# CCP_IO.net
KiCad netlist of a schematic drawn in Altium Designer
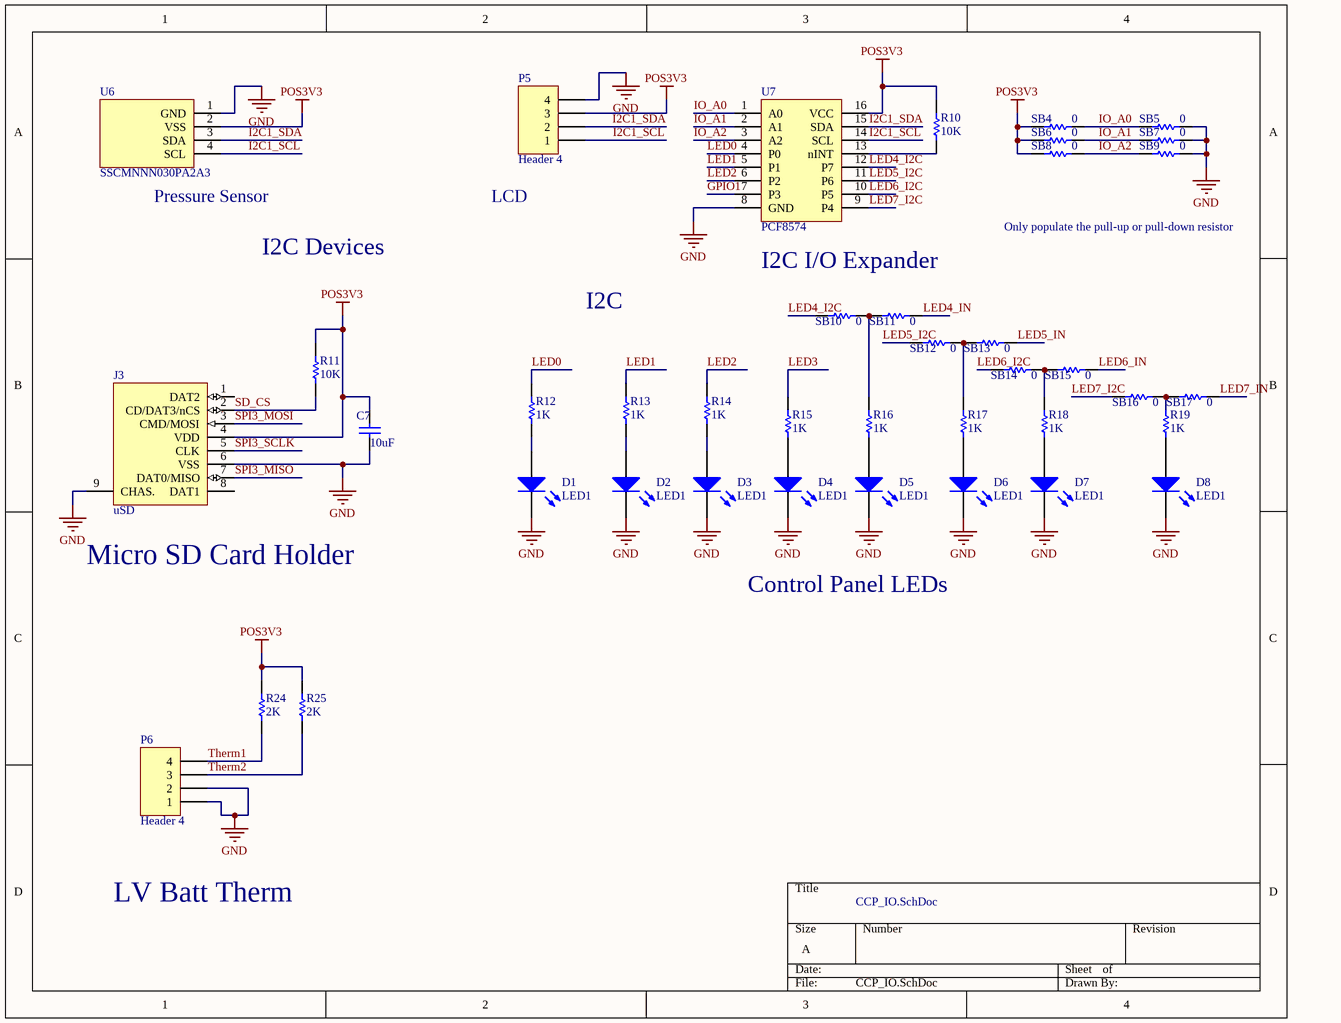
[diagram p0: CCP_IO.SchDoc]

(export (version "E")
  (design (tool "Eeschema 10.0.6"))
  (components
    (comp (ref "C7")
      (value "10uF")
      (footprint "C1206")
      (description "Capacitor")
      (fields (field (name "Comment") "Cap") (field (name "PUBLISHER") "Altium Limited"))
      (libsource (lib "Miscellaneous Devices") (part "Cap"))
    )
    (comp (ref "D1")
      (value "LED1")
      (footprint "2 Pin Jumper")
      (description "Typical RED GaAs LED")
      (fields (field (name "PUBLISHER") "Altium Limited"))
      (libsource (lib "Miscellaneous Devices") (part "LED1"))
    )
    (comp (ref "D2")
      (value "LED1")
      (footprint "2 Pin Jumper")
      (description "Typical RED GaAs LED")
      (fields (field (name "PUBLISHER") "Altium Limited"))
      (libsource (lib "Miscellaneous Devices") (part "LED1"))
    )
    (comp (ref "D3")
      (value "LED1")
      (footprint "2 Pin Jumper")
      (description "Typical RED GaAs LED")
      (fields (field (name "PUBLISHER") "Altium Limited"))
      (libsource (lib "Miscellaneous Devices") (part "LED1"))
    )
    (comp (ref "D4")
      (value "LED1")
      (footprint "2 Pin Jumper")
      (description "Typical RED GaAs LED")
      (fields (field (name "PUBLISHER") "Altium Limited"))
      (libsource (lib "Miscellaneous Devices") (part "LED1"))
    )
    (comp (ref "D5")
      (value "LED1")
      (footprint "2 Pin Jumper")
      (description "Typical RED GaAs LED")
      (fields (field (name "PUBLISHER") "Altium Limited"))
      (libsource (lib "Miscellaneous Devices") (part "LED1"))
    )
    (comp (ref "D6")
      (value "LED1")
      (footprint "2 Pin Jumper")
      (description "Typical RED GaAs LED")
      (fields (field (name "PUBLISHER") "Altium Limited"))
      (libsource (lib "Miscellaneous Devices") (part "LED1"))
    )
    (comp (ref "D7")
      (value "LED1")
      (footprint "2 Pin Jumper")
      (description "Typical RED GaAs LED")
      (fields (field (name "PUBLISHER") "Altium Limited"))
      (libsource (lib "Miscellaneous Devices") (part "LED1"))
    )
    (comp (ref "D8")
      (value "LED1")
      (footprint "2 Pin Jumper")
      (description "Typical RED GaAs LED")
      (fields (field (name "PUBLISHER") "Altium Limited"))
      (libsource (lib "Miscellaneous Devices") (part "LED1"))
    )
    (comp (ref "J3")
      (value "uSD")
      (footprint "MICRO_SD_HOLDER")
      (libsource (lib "connector") (part "SD Card"))
    )
    (comp (ref "P5")
      (value "Header 4")
      (footprint "4POS TERM BLOCK")
      (description "Header, 4-Pin")
      (fields (field (name "PUBLISHER") "Altium Limited"))
      (libsource (lib "Miscellaneous Connectors") (part "Header 4"))
    )
    (comp (ref "P6")
      (value "Header 4")
      (footprint "HDR1X4")
      (description "Header, 4-Pin")
      (fields (field (name "PUBLISHER") "Altium Limited"))
      (libsource (lib "Miscellaneous Connectors") (part "Header 4"))
    )
    (comp (ref "R10")
      (value "10K")
      (footprint "6-0805_M")
      (description "Resistor")
      (fields (field (name "Comment") "Res1") (field (name "PUBLISHER") "Altium Limited"))
      (libsource (lib "Miscellaneous Devices") (part "Res1"))
    )
    (comp (ref "R11")
      (value "10K")
      (footprint "6-0805_M")
      (description "Resistor")
      (fields (field (name "Comment") "Res1") (field (name "PUBLISHER") "Altium Limited"))
      (libsource (lib "Miscellaneous Devices") (part "Res1"))
    )
    (comp (ref "R12")
      (value "1K")
      (footprint "1206")
      (description "Resistor")
      (fields (field (name "Comment") "Res1") (field (name "PUBLISHER") "Altium Limited"))
      (libsource (lib "Miscellaneous Devices") (part "Res1"))
    )
    (comp (ref "R13")
      (value "1K")
      (footprint "1206")
      (description "Resistor")
      (fields (field (name "Comment") "Res1") (field (name "PUBLISHER") "Altium Limited"))
      (libsource (lib "Miscellaneous Devices") (part "Res1"))
    )
    (comp (ref "R14")
      (value "1K")
      (footprint "1206")
      (description "Resistor")
      (fields (field (name "Comment") "Res1") (field (name "PUBLISHER") "Altium Limited"))
      (libsource (lib "Miscellaneous Devices") (part "Res1"))
    )
    (comp (ref "R15")
      (value "1K")
      (footprint "1206")
      (description "Resistor")
      (fields (field (name "Comment") "Res1") (field (name "PUBLISHER") "Altium Limited"))
      (libsource (lib "Miscellaneous Devices") (part "Res1"))
    )
    (comp (ref "R16")
      (value "1K")
      (footprint "1206")
      (description "Resistor")
      (fields (field (name "Comment") "Res1") (field (name "PUBLISHER") "Altium Limited"))
      (libsource (lib "Miscellaneous Devices") (part "Res1"))
    )
    (comp (ref "R17")
      (value "1K")
      (footprint "1206")
      (description "Resistor")
      (fields (field (name "Comment") "Res1") (field (name "PUBLISHER") "Altium Limited"))
      (libsource (lib "Miscellaneous Devices") (part "Res1"))
    )
    (comp (ref "R18")
      (value "1K")
      (footprint "1206")
      (description "Resistor")
      (fields (field (name "Comment") "Res1") (field (name "PUBLISHER") "Altium Limited"))
      (libsource (lib "Miscellaneous Devices") (part "Res1"))
    )
    (comp (ref "R19")
      (value "1K")
      (footprint "1206")
      (description "Resistor")
      (fields (field (name "Comment") "Res1") (field (name "PUBLISHER") "Altium Limited"))
      (libsource (lib "Miscellaneous Devices") (part "Res1"))
    )
    (comp (ref "R24")
      (value "2K")
      (footprint "6-0805_M")
      (description "Resistor")
      (fields (field (name "Comment") "Res1") (field (name "PUBLISHER") "Altium Limited"))
      (libsource (lib "Miscellaneous Devices") (part "Res1"))
    )
    (comp (ref "R25")
      (value "2K")
      (footprint "6-0805_M")
      (description "Resistor")
      (fields (field (name "Comment") "Res1") (field (name "PUBLISHER") "Altium Limited"))
      (libsource (lib "Miscellaneous Devices") (part "Res1"))
    )
    (comp (ref "SB4")
      (value "0")
      (footprint "6-0805_M")
      (description "Resistor")
      (fields (field (name "Comment") "Res1") (field (name "PUBLISHER") "Altium Limited"))
      (libsource (lib "Miscellaneous Devices") (part "Res1"))
    )
    (comp (ref "SB5")
      (value "0")
      (footprint "6-0805_M")
      (description "Resistor")
      (fields (field (name "Comment") "Res1") (field (name "PUBLISHER") "Altium Limited"))
      (libsource (lib "Miscellaneous Devices") (part "Res1"))
    )
    (comp (ref "SB6")
      (value "0")
      (footprint "6-0805_M")
      (description "Resistor")
      (fields (field (name "Comment") "Res1") (field (name "PUBLISHER") "Altium Limited"))
      (libsource (lib "Miscellaneous Devices") (part "Res1"))
    )
    (comp (ref "SB7")
      (value "0")
      (footprint "6-0805_M")
      (description "Resistor")
      (fields (field (name "Comment") "Res1") (field (name "PUBLISHER") "Altium Limited"))
      (libsource (lib "Miscellaneous Devices") (part "Res1"))
    )
    (comp (ref "SB8")
      (value "0")
      (footprint "6-0805_M")
      (description "Resistor")
      (fields (field (name "Comment") "Res1") (field (name "PUBLISHER") "Altium Limited"))
      (libsource (lib "Miscellaneous Devices") (part "Res1"))
    )
    (comp (ref "SB9")
      (value "0")
      (footprint "6-0805_M")
      (description "Resistor")
      (fields (field (name "Comment") "Res1") (field (name "PUBLISHER") "Altium Limited"))
      (libsource (lib "Miscellaneous Devices") (part "Res1"))
    )
    (comp (ref "SB10")
      (value "0")
      (footprint "6-0805_M")
      (description "Resistor")
      (fields (field (name "Comment") "Res1") (field (name "PUBLISHER") "Altium Limited"))
      (libsource (lib "Miscellaneous Devices") (part "Res1"))
    )
    (comp (ref "SB11")
      (value "0")
      (footprint "6-0805_M")
      (description "Resistor")
      (fields (field (name "Comment") "Res1") (field (name "PUBLISHER") "Altium Limited"))
      (libsource (lib "Miscellaneous Devices") (part "Res1"))
    )
    (comp (ref "SB12")
      (value "0")
      (footprint "6-0805_M")
      (description "Resistor")
      (fields (field (name "Comment") "Res1") (field (name "PUBLISHER") "Altium Limited"))
      (libsource (lib "Miscellaneous Devices") (part "Res1"))
    )
    (comp (ref "SB13")
      (value "0")
      (footprint "6-0805_M")
      (description "Resistor")
      (fields (field (name "Comment") "Res1") (field (name "PUBLISHER") "Altium Limited"))
      (libsource (lib "Miscellaneous Devices") (part "Res1"))
    )
    (comp (ref "SB14")
      (value "0")
      (footprint "6-0805_M")
      (description "Resistor")
      (fields (field (name "Comment") "Res1") (field (name "PUBLISHER") "Altium Limited"))
      (libsource (lib "Miscellaneous Devices") (part "Res1"))
    )
    (comp (ref "SB15")
      (value "0")
      (footprint "6-0805_M")
      (description "Resistor")
      (fields (field (name "Comment") "Res1") (field (name "PUBLISHER") "Altium Limited"))
      (libsource (lib "Miscellaneous Devices") (part "Res1"))
    )
    (comp (ref "SB16")
      (value "0")
      (footprint "6-0805_M")
      (description "Resistor")
      (fields (field (name "Comment") "Res1") (field (name "PUBLISHER") "Altium Limited"))
      (libsource (lib "Miscellaneous Devices") (part "Res1"))
    )
    (comp (ref "SB17")
      (value "0")
      (footprint "6-0805_M")
      (description "Resistor")
      (fields (field (name "Comment") "Res1") (field (name "PUBLISHER") "Altium Limited"))
      (libsource (lib "Miscellaneous Devices") (part "Res1"))
    )
    (comp (ref "U6")
      (value "SSCMNNN030PA2A3")
      (footprint "8-SMT")
      (description "Honeywell Digital Pressure Sensor")
      (libsource (lib "ic") (part "SSCMNNN030PA2A3"))
    )
    (comp (ref "U7")
      (value "PCF8574")
      (footprint "16-SOIC")
      (description "I2C I/O Expander")
      (libsource (lib "ic") (part "PCF8574"))
    )
  )
  (nets
    (net (code "1") (name "/GPIO1") (class "Default")
      (node (ref "U7") (pin "7") (pinfunction "P3_7") (pintype "passive"))
    )
    (net (code "2") (name "/I2C1_SCL") (class "Default")
      (node (ref "P5") (pin "1") (pinfunction "1_1") (pintype "passive"))
      (node (ref "U6") (pin "4") (pinfunction "SCL_4") (pintype "passive"))
      (node (ref "U7") (pin "14") (pinfunction "SCL_14") (pintype "passive"))
    )
    (net (code "3") (name "/I2C1_SDA") (class "Default")
      (node (ref "P5") (pin "2") (pinfunction "2_2") (pintype "passive"))
      (node (ref "U6") (pin "3") (pinfunction "SDA_3") (pintype "passive"))
      (node (ref "U7") (pin "15") (pinfunction "SDA_15") (pintype "passive"))
    )
    (net (code "4") (name "/IO_A0") (class "Default")
      (node (ref "SB4") (pin "1") (pinfunction "1_1") (pintype "passive"))
      (node (ref "SB5") (pin "2") (pinfunction "2_2") (pintype "passive"))
      (node (ref "U7") (pin "1") (pinfunction "A0_1") (pintype "passive"))
    )
    (net (code "5") (name "/IO_A1") (class "Default")
      (node (ref "SB6") (pin "1") (pinfunction "1_1") (pintype "passive"))
      (node (ref "SB7") (pin "2") (pinfunction "2_2") (pintype "passive"))
      (node (ref "U7") (pin "2") (pinfunction "A1_2") (pintype "passive"))
    )
    (net (code "6") (name "/IO_A2") (class "Default")
      (node (ref "SB8") (pin "1") (pinfunction "1_1") (pintype "passive"))
      (node (ref "SB9") (pin "2") (pinfunction "2_2") (pintype "passive"))
      (node (ref "U7") (pin "3") (pinfunction "A2_3") (pintype "passive"))
    )
    (net (code "7") (name "/LED0") (class "Default")
      (node (ref "R12") (pin "2") (pinfunction "2_2") (pintype "passive"))
      (node (ref "U7") (pin "4") (pinfunction "P0_4") (pintype "passive"))
    )
    (net (code "8") (name "/LED1") (class "Default")
      (node (ref "R13") (pin "2") (pinfunction "2_2") (pintype "passive"))
      (node (ref "U7") (pin "5") (pinfunction "P1_5") (pintype "passive"))
    )
    (net (code "9") (name "/LED2") (class "Default")
      (node (ref "R14") (pin "2") (pinfunction "2_2") (pintype "passive"))
      (node (ref "U7") (pin "6") (pinfunction "P2_6") (pintype "passive"))
    )
    (net (code "10") (name "/LED3") (class "Default")
      (node (ref "R15") (pin "2") (pinfunction "2_2") (pintype "passive"))
    )
    (net (code "11") (name "/LED4_I2C") (class "Default")
      (node (ref "SB10") (pin "2") (pinfunction "2_2") (pintype "passive"))
      (node (ref "U7") (pin "12") (pinfunction "P7_12") (pintype "passive"))
    )
    (net (code "12") (name "/LED4_IN") (class "Default")
      (node (ref "SB11") (pin "1") (pinfunction "1_1") (pintype "passive"))
    )
    (net (code "13") (name "/LED5_I2C") (class "Default")
      (node (ref "SB12") (pin "2") (pinfunction "2_2") (pintype "passive"))
      (node (ref "U7") (pin "11") (pinfunction "P6_11") (pintype "passive"))
    )
    (net (code "14") (name "/LED5_IN") (class "Default")
      (node (ref "SB13") (pin "1") (pinfunction "1_1") (pintype "passive"))
    )
    (net (code "15") (name "/LED6_I2C") (class "Default")
      (node (ref "SB14") (pin "2") (pinfunction "2_2") (pintype "passive"))
      (node (ref "U7") (pin "10") (pinfunction "P5_10") (pintype "passive"))
    )
    (net (code "16") (name "/LED6_IN") (class "Default")
      (node (ref "SB15") (pin "1") (pinfunction "1_1") (pintype "passive"))
    )
    (net (code "17") (name "/LED7_I2C") (class "Default")
      (node (ref "SB16") (pin "2") (pinfunction "2_2") (pintype "passive"))
      (node (ref "U7") (pin "9") (pinfunction "P4_9") (pintype "passive"))
    )
    (net (code "18") (name "/LED7_IN") (class "Default")
      (node (ref "SB17") (pin "1") (pinfunction "1_1") (pintype "passive"))
    )
    (net (code "19") (name "/SD_CS") (class "Default")
      (node (ref "J3") (pin "2") (pinfunction "CD/DAT3/nCS_2") (pintype "bidirectional"))
      (node (ref "R11") (pin "2") (pinfunction "2_2") (pintype "passive"))
    )
    (net (code "20") (name "/SPI3_MISO") (class "Default")
      (node (ref "J3") (pin "7") (pinfunction "DAT0/MISO_7") (pintype "bidirectional"))
    )
    (net (code "21") (name "/SPI3_MOSI") (class "Default")
      (node (ref "J3") (pin "3") (pinfunction "CMD/MOSI_3") (pintype "input"))
    )
    (net (code "22") (name "/SPI3_SCLK") (class "Default")
      (node (ref "J3") (pin "5") (pinfunction "CLK_5") (pintype "passive"))
    )
    (net (code "23") (name "/Therm1") (class "Default")
      (node (ref "P6") (pin "4") (pinfunction "4_4") (pintype "passive"))
      (node (ref "R24") (pin "1") (pinfunction "1_1") (pintype "passive"))
    )
    (net (code "24") (name "/Therm2") (class "Default")
      (node (ref "P6") (pin "3") (pinfunction "3_3") (pintype "passive"))
      (node (ref "R25") (pin "1") (pinfunction "1_1") (pintype "passive"))
    )
    (net (code "25") (name "GND") (class "Default")
      (node (ref "C7") (pin "1") (pinfunction "1_1") (pintype "passive"))
      (node (ref "D1") (pin "2") (pinfunction "K_2") (pintype "passive"))
      (node (ref "D2") (pin "2") (pinfunction "K_2") (pintype "passive"))
      (node (ref "D3") (pin "2") (pinfunction "K_2") (pintype "passive"))
      (node (ref "D4") (pin "2") (pinfunction "K_2") (pintype "passive"))
      (node (ref "D5") (pin "2") (pinfunction "K_2") (pintype "passive"))
      (node (ref "D6") (pin "2") (pinfunction "K_2") (pintype "passive"))
      (node (ref "D7") (pin "2") (pinfunction "K_2") (pintype "passive"))
      (node (ref "D8") (pin "2") (pinfunction "K_2") (pintype "passive"))
      (node (ref "J3") (pin "6") (pinfunction "VSS_6") (pintype "passive"))
      (node (ref "J3") (pin "9") (pinfunction "CHAS._9") (pintype "passive"))
      (node (ref "P5") (pin "4") (pinfunction "4_4") (pintype "passive"))
      (node (ref "P6") (pin "1") (pinfunction "1_1") (pintype "passive"))
      (node (ref "P6") (pin "2") (pinfunction "2_2") (pintype "passive"))
      (node (ref "SB5") (pin "1") (pinfunction "1_1") (pintype "passive"))
      (node (ref "SB7") (pin "1") (pinfunction "1_1") (pintype "passive"))
      (node (ref "SB9") (pin "1") (pinfunction "1_1") (pintype "passive"))
      (node (ref "U6") (pin "1") (pinfunction "GND_1") (pintype "power_in"))
      (node (ref "U7") (pin "8") (pinfunction "GND_8") (pintype "passive"))
    )
    (net (code "26") (name "Net-(D1-A)") (class "Default")
      (node (ref "D1") (pin "1") (pinfunction "A_1") (pintype "passive"))
      (node (ref "R12") (pin "1") (pinfunction "1_1") (pintype "passive"))
    )
    (net (code "27") (name "Net-(D2-A)") (class "Default")
      (node (ref "D2") (pin "1") (pinfunction "A_1") (pintype "passive"))
      (node (ref "R13") (pin "1") (pinfunction "1_1") (pintype "passive"))
    )
    (net (code "28") (name "Net-(D3-A)") (class "Default")
      (node (ref "D3") (pin "1") (pinfunction "A_1") (pintype "passive"))
      (node (ref "R14") (pin "1") (pinfunction "1_1") (pintype "passive"))
    )
    (net (code "29") (name "Net-(D4-A)") (class "Default")
      (node (ref "D4") (pin "1") (pinfunction "A_1") (pintype "passive"))
      (node (ref "R15") (pin "1") (pinfunction "1_1") (pintype "passive"))
    )
    (net (code "30") (name "Net-(D5-A)") (class "Default")
      (node (ref "D5") (pin "1") (pinfunction "A_1") (pintype "passive"))
      (node (ref "R16") (pin "1") (pinfunction "1_1") (pintype "passive"))
    )
    (net (code "31") (name "Net-(D6-A)") (class "Default")
      (node (ref "D6") (pin "1") (pinfunction "A_1") (pintype "passive"))
      (node (ref "R17") (pin "1") (pinfunction "1_1") (pintype "passive"))
    )
    (net (code "32") (name "Net-(D7-A)") (class "Default")
      (node (ref "D7") (pin "1") (pinfunction "A_1") (pintype "passive"))
      (node (ref "R18") (pin "1") (pinfunction "1_1") (pintype "passive"))
    )
    (net (code "33") (name "Net-(D8-A)") (class "Default")
      (node (ref "D8") (pin "1") (pinfunction "A_1") (pintype "passive"))
      (node (ref "R19") (pin "1") (pinfunction "1_1") (pintype "passive"))
    )
    (net (code "34") (name "Net-(R16-Pad2)") (class "Default")
      (node (ref "R16") (pin "2") (pinfunction "2_2") (pintype "passive"))
      (node (ref "SB10") (pin "1") (pinfunction "1_1") (pintype "passive"))
      (node (ref "SB11") (pin "2") (pinfunction "2_2") (pintype "passive"))
    )
    (net (code "35") (name "Net-(R17-Pad2)") (class "Default")
      (node (ref "R17") (pin "2") (pinfunction "2_2") (pintype "passive"))
      (node (ref "SB12") (pin "1") (pinfunction "1_1") (pintype "passive"))
      (node (ref "SB13") (pin "2") (pinfunction "2_2") (pintype "passive"))
    )
    (net (code "36") (name "Net-(R18-Pad2)") (class "Default")
      (node (ref "R18") (pin "2") (pinfunction "2_2") (pintype "passive"))
      (node (ref "SB14") (pin "1") (pinfunction "1_1") (pintype "passive"))
      (node (ref "SB15") (pin "2") (pinfunction "2_2") (pintype "passive"))
    )
    (net (code "37") (name "Net-(R19-Pad2)") (class "Default")
      (node (ref "R19") (pin "2") (pinfunction "2_2") (pintype "passive"))
      (node (ref "SB16") (pin "1") (pinfunction "1_1") (pintype "passive"))
      (node (ref "SB17") (pin "2") (pinfunction "2_2") (pintype "passive"))
    )
    (net (code "38") (name "Net-(U7-nINT)") (class "Default")
      (node (ref "R10") (pin "1") (pinfunction "1_1") (pintype "passive"))
      (node (ref "U7") (pin "13") (pinfunction "nINT_13") (pintype "passive"))
    )
    (net (code "39") (name "POS3V3") (class "Default")
      (node (ref "C7") (pin "2") (pinfunction "2_2") (pintype "passive"))
      (node (ref "J3") (pin "4") (pinfunction "VDD_4") (pintype "power_in"))
      (node (ref "P5") (pin "3") (pinfunction "3_3") (pintype "passive"))
      (node (ref "R10") (pin "2") (pinfunction "2_2") (pintype "passive"))
      (node (ref "R11") (pin "1") (pinfunction "1_1") (pintype "passive"))
      (node (ref "R24") (pin "2") (pinfunction "2_2") (pintype "passive"))
      (node (ref "R25") (pin "2") (pinfunction "2_2") (pintype "passive"))
      (node (ref "SB4") (pin "2") (pinfunction "2_2") (pintype "passive"))
      (node (ref "SB6") (pin "2") (pinfunction "2_2") (pintype "passive"))
      (node (ref "SB8") (pin "2") (pinfunction "2_2") (pintype "passive"))
      (node (ref "U6") (pin "2") (pinfunction "VSS_2") (pintype "power_in"))
      (node (ref "U7") (pin "16") (pinfunction "VCC_16") (pintype "passive"))
    )
    (net (code "40") (name "unconnected-(J3-DAT1-Pad8)") (class "Default")
      (node (ref "J3") (pin "8") (pinfunction "DAT1_8") (pintype "passive"))
    )
    (net (code "41") (name "unconnected-(J3-DAT2-Pad1)") (class "Default")
      (node (ref "J3") (pin "1") (pinfunction "DAT2_1") (pintype "bidirectional"))
    )
  )
)
